# dsau-interfaces.net
KiCad netlist of a schematic drawn in Altium Designer
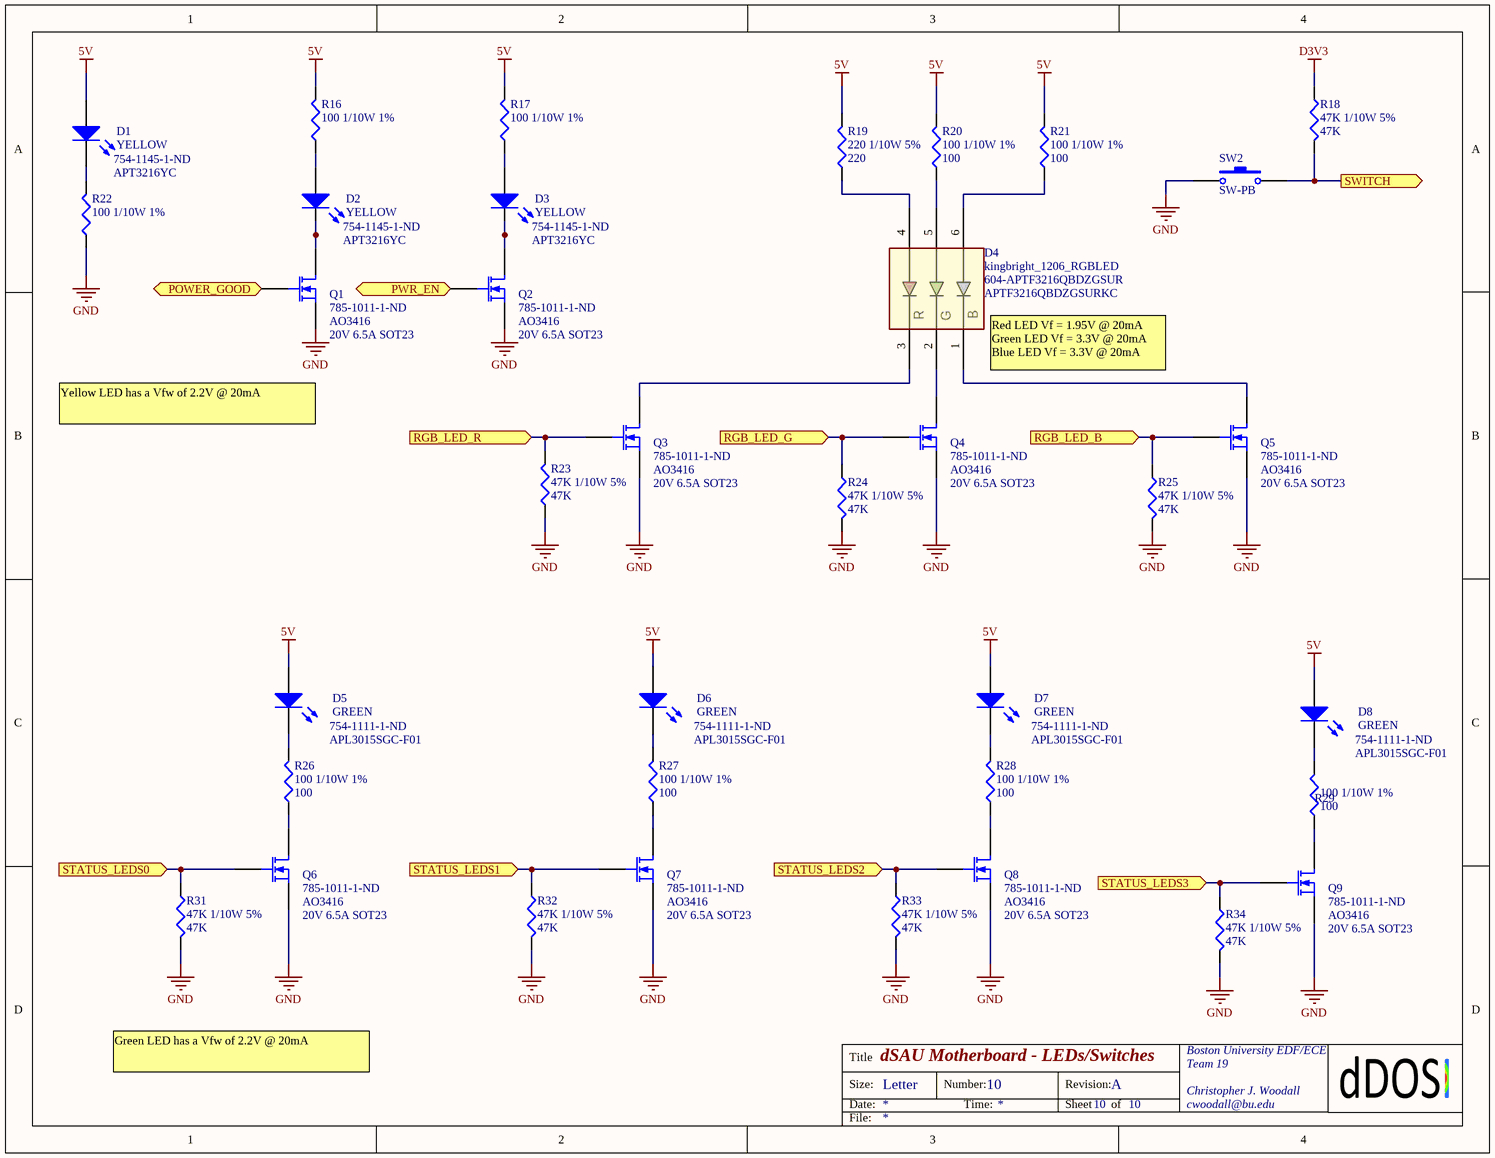
[diagram p0: dsau-interfaces.SchDoc]

(export (version "E")
  (design (tool "Eeschema 10.0.6"))
  (components
    (comp (ref "D1")
      (value "YELLOW")
      (footprint "LED3216X08M")
      (description "Typical INFRARED GaAs LED")
      (fields
        (field (name "MANUFACTURER") "Kingbright Company LLC")
        (field (name "MANUFACTURER PART NUMBER") "APT3216YC")
        (field (name "SUPPLIER PART NUMBER 1") "754-1145-1-ND")
        (field (name "PUBLISHER") "Altium Limited")
      )
      (libsource (lib "Miscellaneous Devices") (part "LED0"))
    )
    (comp (ref "D2")
      (value "YELLOW")
      (footprint "LED3216X08M")
      (description "Typical INFRARED GaAs LED")
      (fields
        (field (name "MANUFACTURER") "Kingbright Company LLC")
        (field (name "MANUFACTURER PART NUMBER") "APT3216YC")
        (field (name "SUPPLIER PART NUMBER 1") "754-1145-1-ND")
        (field (name "PUBLISHER") "Altium Limited")
      )
      (libsource (lib "Miscellaneous Devices") (part "LED0"))
    )
    (comp (ref "D3")
      (value "YELLOW")
      (footprint "LED3216X08M")
      (description "Typical INFRARED GaAs LED")
      (fields
        (field (name "MANUFACTURER") "Kingbright Company LLC")
        (field (name "MANUFACTURER PART NUMBER") "APT3216YC")
        (field (name "SUPPLIER PART NUMBER 1") "754-1145-1-ND")
        (field (name "PUBLISHER") "Altium Limited")
      )
      (libsource (lib "Miscellaneous Devices") (part "LED0"))
    )
    (comp (ref "D4")
      (value "kingbright_1206_RGBLED")
      (footprint "RGBLED_1206_KINGSBRIGHT")
      (fields
        (field (name "SUPPLIER PART NUMBER 1") "604-APTF3216QBDZGSUR")
        (field (name "MANUFACTURER") "Kingbright")
        (field (name "MANUFACTURER PART NUMBER") "APTF3216QBDZGSURKC")
      )
      (libsource (lib "dsau-motherboard") (part "kingbright_1206_RGBLED"))
    )
    (comp (ref "D5")
      (value "GREEN")
      (footprint "LED3216X08M")
      (description "Typical INFRARED GaAs LED")
      (fields
        (field (name "MANUFACTURER") "Kingbright Company LLC")
        (field (name "MANUFACTURER PART NUMBER") "APL3015SGC-F01")
        (field (name "SUPPLIER PART NUMBER 1") "754-1111-1-ND")
        (field (name "PUBLISHER") "Altium Limited")
      )
      (libsource (lib "Miscellaneous Devices") (part "LED0"))
    )
    (comp (ref "D6")
      (value "GREEN")
      (footprint "LED3216X08M")
      (description "Typical INFRARED GaAs LED")
      (fields
        (field (name "MANUFACTURER") "Kingbright Company LLC")
        (field (name "MANUFACTURER PART NUMBER") "APL3015SGC-F01")
        (field (name "SUPPLIER PART NUMBER 1") "754-1111-1-ND")
        (field (name "PUBLISHER") "Altium Limited")
      )
      (libsource (lib "Miscellaneous Devices") (part "LED0"))
    )
    (comp (ref "D7")
      (value "GREEN")
      (footprint "LED3216X08M")
      (description "Typical INFRARED GaAs LED")
      (fields
        (field (name "MANUFACTURER") "Kingbright Company LLC")
        (field (name "MANUFACTURER PART NUMBER") "APL3015SGC-F01")
        (field (name "SUPPLIER PART NUMBER 1") "754-1111-1-ND")
        (field (name "PUBLISHER") "Altium Limited")
      )
      (libsource (lib "Miscellaneous Devices") (part "LED0"))
    )
    (comp (ref "D8")
      (value "GREEN")
      (footprint "LED3216X08M")
      (description "Typical INFRARED GaAs LED")
      (fields
        (field (name "MANUFACTURER") "Kingbright Company LLC")
        (field (name "MANUFACTURER PART NUMBER") "APL3015SGC-F01")
        (field (name "SUPPLIER PART NUMBER 1") "754-1111-1-ND")
        (field (name "PUBLISHER") "Altium Limited")
      )
      (libsource (lib "Miscellaneous Devices") (part "LED0"))
    )
    (comp (ref "Q1")
      (value "20V 6.5A SOT23")
      (footprint "SOT95P305X200-3M")
      (description "N-Channel MOSFET 1.8V Logic Level")
      (fields
        (field (name "MANUFACTURER") "Alpha & Omega Semiconductor Inc")
        (field (name "MANUFACTURER PART NUMBER") "AO3416")
        (field (name "SUPPLIER PART NUMBER 1") "785-1011-1-ND")
        (field (name "PUBLISHER") "Altium Limited")
      )
      (libsource (lib "Miscellaneous Devices") (part "MOSFET-N"))
    )
    (comp (ref "Q2")
      (value "20V 6.5A SOT23")
      (footprint "SOT95P305X200-3M")
      (description "N-Channel MOSFET 1.8V Logic Level")
      (fields
        (field (name "MANUFACTURER") "Alpha & Omega Semiconductor Inc")
        (field (name "MANUFACTURER PART NUMBER") "AO3416")
        (field (name "SUPPLIER PART NUMBER 1") "785-1011-1-ND")
        (field (name "PUBLISHER") "Altium Limited")
      )
      (libsource (lib "Miscellaneous Devices") (part "MOSFET-N"))
    )
    (comp (ref "Q3")
      (value "20V 6.5A SOT23")
      (footprint "SOT95P305X200-3M")
      (description "N-Channel MOSFET 1.8V Logic Level")
      (fields
        (field (name "MANUFACTURER") "Alpha & Omega Semiconductor Inc")
        (field (name "MANUFACTURER PART NUMBER") "AO3416")
        (field (name "SUPPLIER PART NUMBER 1") "785-1011-1-ND")
        (field (name "PUBLISHER") "Altium Limited")
      )
      (libsource (lib "Miscellaneous Devices") (part "MOSFET-N"))
    )
    (comp (ref "Q4")
      (value "20V 6.5A SOT23")
      (footprint "SOT95P305X200-3M")
      (description "N-Channel MOSFET 1.8V Logic Level")
      (fields
        (field (name "MANUFACTURER") "Alpha & Omega Semiconductor Inc")
        (field (name "MANUFACTURER PART NUMBER") "AO3416")
        (field (name "SUPPLIER PART NUMBER 1") "785-1011-1-ND")
        (field (name "PUBLISHER") "Altium Limited")
      )
      (libsource (lib "Miscellaneous Devices") (part "MOSFET-N"))
    )
    (comp (ref "Q5")
      (value "20V 6.5A SOT23")
      (footprint "SOT95P305X200-3M")
      (description "N-Channel MOSFET 1.8V Logic Level")
      (fields
        (field (name "MANUFACTURER") "Alpha & Omega Semiconductor Inc")
        (field (name "MANUFACTURER PART NUMBER") "AO3416")
        (field (name "SUPPLIER PART NUMBER 1") "785-1011-1-ND")
        (field (name "PUBLISHER") "Altium Limited")
      )
      (libsource (lib "Miscellaneous Devices") (part "MOSFET-N"))
    )
    (comp (ref "Q6")
      (value "20V 6.5A SOT23")
      (footprint "SOT95P305X200-3M")
      (description "N-Channel MOSFET 1.8V Logic Level")
      (fields
        (field (name "MANUFACTURER") "Alpha & Omega Semiconductor Inc")
        (field (name "MANUFACTURER PART NUMBER") "AO3416")
        (field (name "SUPPLIER PART NUMBER 1") "785-1011-1-ND")
        (field (name "PUBLISHER") "Altium Limited")
      )
      (libsource (lib "Miscellaneous Devices") (part "MOSFET-N"))
    )
    (comp (ref "Q7")
      (value "20V 6.5A SOT23")
      (footprint "SOT95P305X200-3M")
      (description "N-Channel MOSFET 1.8V Logic Level")
      (fields
        (field (name "MANUFACTURER") "Alpha & Omega Semiconductor Inc")
        (field (name "MANUFACTURER PART NUMBER") "AO3416")
        (field (name "SUPPLIER PART NUMBER 1") "785-1011-1-ND")
        (field (name "PUBLISHER") "Altium Limited")
      )
      (libsource (lib "Miscellaneous Devices") (part "MOSFET-N"))
    )
    (comp (ref "Q8")
      (value "20V 6.5A SOT23")
      (footprint "SOT95P305X200-3M")
      (description "N-Channel MOSFET 1.8V Logic Level")
      (fields
        (field (name "MANUFACTURER") "Alpha & Omega Semiconductor Inc")
        (field (name "MANUFACTURER PART NUMBER") "AO3416")
        (field (name "SUPPLIER PART NUMBER 1") "785-1011-1-ND")
        (field (name "PUBLISHER") "Altium Limited")
      )
      (libsource (lib "Miscellaneous Devices") (part "MOSFET-N"))
    )
    (comp (ref "Q9")
      (value "20V 6.5A SOT23")
      (footprint "SOT95P305X200-3M")
      (description "N-Channel MOSFET 1.8V Logic Level")
      (fields
        (field (name "MANUFACTURER") "Alpha & Omega Semiconductor Inc")
        (field (name "MANUFACTURER PART NUMBER") "AO3416")
        (field (name "SUPPLIER PART NUMBER 1") "785-1011-1-ND")
        (field (name "PUBLISHER") "Altium Limited")
      )
      (libsource (lib "Miscellaneous Devices") (part "MOSFET-N"))
    )
    (comp (ref "R16")
      (value "100 1/10W 1%")
      (footprint "RESC1608L")
      (description "Resistor")
      (fields
        (field (name "MANUFACTURER") "Yageo")
        (field (name "MANUFACTURER PART NUMBER") "RC0603FR-07100RL")
        (field (name "PUBLISHER") "Altium Limited")
      )
      (libsource (lib "Miscellaneous Devices") (part "Res3"))
    )
    (comp (ref "R17")
      (value "100 1/10W 1%")
      (footprint "RESC1608L")
      (description "Resistor")
      (fields
        (field (name "MANUFACTURER") "Yageo")
        (field (name "MANUFACTURER PART NUMBER") "RC0603FR-07100RL")
        (field (name "PUBLISHER") "Altium Limited")
      )
      (libsource (lib "Miscellaneous Devices") (part "Res3"))
    )
    (comp (ref "R18")
      (value "47K 1/10W 5%")
      (footprint "RESC1608L")
      (description "Resistor")
      (fields
        (field (name "ALTIUM_VALUE") "47K")
        (field (name "MANUFACTURER") "Yageo")
        (field (name "MANUFACTURER PART NUMBER") "311-47kGRCT-ND")
        (field (name "PUBLISHER") "Altium Limited")
      )
      (libsource (lib "Miscellaneous Devices") (part "Res3"))
    )
    (comp (ref "R19")
      (value "220 1/10W 5%")
      (footprint "RESC1608L")
      (description "Resistor")
      (fields
        (field (name "ALTIUM_VALUE") "220")
        (field (name "MANUFACTURER") "Yageo")
        (field (name "MANUFACTURER PART NUMBER") "RC0603FR-07220RL")
        (field (name "PUBLISHER") "Altium Limited")
      )
      (libsource (lib "Miscellaneous Devices") (part "Res3"))
    )
    (comp (ref "R20")
      (value "100 1/10W 1%")
      (footprint "RESC1608L")
      (description "Resistor")
      (fields
        (field (name "ALTIUM_VALUE") "100")
        (field (name "MANUFACTURER") "Yageo")
        (field (name "MANUFACTURER PART NUMBER") "RC0603FR-07100RL")
        (field (name "PUBLISHER") "Altium Limited")
      )
      (libsource (lib "Miscellaneous Devices") (part "Res3"))
    )
    (comp (ref "R21")
      (value "100 1/10W 1%")
      (footprint "RESC1608L")
      (description "Resistor")
      (fields
        (field (name "ALTIUM_VALUE") "100")
        (field (name "MANUFACTURER") "Yageo")
        (field (name "MANUFACTURER PART NUMBER") "RC0603FR-07100RL")
        (field (name "PUBLISHER") "Altium Limited")
      )
      (libsource (lib "Miscellaneous Devices") (part "Res3"))
    )
    (comp (ref "R22")
      (value "100 1/10W 1%")
      (footprint "RESC1608L")
      (description "Resistor")
      (fields
        (field (name "MANUFACTURER") "Yageo")
        (field (name "MANUFACTURER PART NUMBER") "RC0603FR-07100RL")
        (field (name "PUBLISHER") "Altium Limited")
      )
      (libsource (lib "Miscellaneous Devices") (part "Res3"))
    )
    (comp (ref "R23")
      (value "47K 1/10W 5%")
      (footprint "RESC1608L")
      (description "Resistor")
      (fields
        (field (name "ALTIUM_VALUE") "47K")
        (field (name "MANUFACTURER") "Yageo")
        (field (name "MANUFACTURER PART NUMBER") "311-47kGRCT-ND")
        (field (name "PUBLISHER") "Altium Limited")
      )
      (libsource (lib "Miscellaneous Devices") (part "Res3"))
    )
    (comp (ref "R24")
      (value "47K 1/10W 5%")
      (footprint "RESC1608L")
      (description "Resistor")
      (fields
        (field (name "ALTIUM_VALUE") "47K")
        (field (name "MANUFACTURER") "Yageo")
        (field (name "MANUFACTURER PART NUMBER") "311-47kGRCT-ND")
        (field (name "PUBLISHER") "Altium Limited")
      )
      (libsource (lib "Miscellaneous Devices") (part "Res3"))
    )
    (comp (ref "R25")
      (value "47K 1/10W 5%")
      (footprint "RESC1608L")
      (description "Resistor")
      (fields
        (field (name "ALTIUM_VALUE") "47K")
        (field (name "MANUFACTURER") "Yageo")
        (field (name "MANUFACTURER PART NUMBER") "311-47kGRCT-ND")
        (field (name "PUBLISHER") "Altium Limited")
      )
      (libsource (lib "Miscellaneous Devices") (part "Res3"))
    )
    (comp (ref "R26")
      (value "100 1/10W 1%")
      (footprint "RESC1608L")
      (description "Resistor")
      (fields
        (field (name "ALTIUM_VALUE") "100")
        (field (name "MANUFACTURER") "Yageo")
        (field (name "MANUFACTURER PART NUMBER") "RC0603FR-07100RL")
        (field (name "PUBLISHER") "Altium Limited")
      )
      (libsource (lib "Miscellaneous Devices") (part "Res3"))
    )
    (comp (ref "R27")
      (value "100 1/10W 1%")
      (footprint "RESC1608L")
      (description "Resistor")
      (fields
        (field (name "ALTIUM_VALUE") "100")
        (field (name "MANUFACTURER") "Yageo")
        (field (name "MANUFACTURER PART NUMBER") "RC0603FR-07100RL")
        (field (name "PUBLISHER") "Altium Limited")
      )
      (libsource (lib "Miscellaneous Devices") (part "Res3"))
    )
    (comp (ref "R28")
      (value "100 1/10W 1%")
      (footprint "RESC1608L")
      (description "Resistor")
      (fields
        (field (name "ALTIUM_VALUE") "100")
        (field (name "MANUFACTURER") "Yageo")
        (field (name "MANUFACTURER PART NUMBER") "RC0603FR-07100RL")
        (field (name "PUBLISHER") "Altium Limited")
      )
      (libsource (lib "Miscellaneous Devices") (part "Res3"))
    )
    (comp (ref "R29")
      (value "100 1/10W 1%")
      (footprint "RESC1608L")
      (description "Resistor")
      (fields
        (field (name "ALTIUM_VALUE") "100")
        (field (name "MANUFACTURER") "Yageo")
        (field (name "MANUFACTURER PART NUMBER") "RC0603FR-07100RL")
        (field (name "PUBLISHER") "Altium Limited")
      )
      (libsource (lib "Miscellaneous Devices") (part "Res3"))
    )
    (comp (ref "R31")
      (value "47K 1/10W 5%")
      (footprint "RESC1608L")
      (description "Resistor")
      (fields
        (field (name "ALTIUM_VALUE") "47K")
        (field (name "MANUFACTURER") "Yageo")
        (field (name "MANUFACTURER PART NUMBER") "311-47kGRCT-ND")
        (field (name "PUBLISHER") "Altium Limited")
      )
      (libsource (lib "Miscellaneous Devices") (part "Res3"))
    )
    (comp (ref "R32")
      (value "47K 1/10W 5%")
      (footprint "RESC1608L")
      (description "Resistor")
      (fields
        (field (name "ALTIUM_VALUE") "47K")
        (field (name "MANUFACTURER") "Yageo")
        (field (name "MANUFACTURER PART NUMBER") "311-47kGRCT-ND")
        (field (name "PUBLISHER") "Altium Limited")
      )
      (libsource (lib "Miscellaneous Devices") (part "Res3"))
    )
    (comp (ref "R33")
      (value "47K 1/10W 5%")
      (footprint "RESC1608L")
      (description "Resistor")
      (fields
        (field (name "ALTIUM_VALUE") "47K")
        (field (name "MANUFACTURER") "Yageo")
        (field (name "MANUFACTURER PART NUMBER") "311-47kGRCT-ND")
        (field (name "PUBLISHER") "Altium Limited")
      )
      (libsource (lib "Miscellaneous Devices") (part "Res3"))
    )
    (comp (ref "R34")
      (value "47K 1/10W 5%")
      (footprint "RESC1608L")
      (description "Resistor")
      (fields
        (field (name "ALTIUM_VALUE") "47K")
        (field (name "MANUFACTURER") "Yageo")
        (field (name "MANUFACTURER PART NUMBER") "311-47kGRCT-ND")
        (field (name "PUBLISHER") "Altium Limited")
      )
      (libsource (lib "Miscellaneous Devices") (part "Res3"))
    )
    (comp (ref "SW2")
      (value "SW-PB")
      (footprint "SPST_SW_FSM4JH")
      (description "Switch")
      (fields
        (field (name "MANUFACTURER") "TE Connectivity")
        (field (name "MANUFACTURER PART NUMBER") "FSM4JH")
        (field (name "PUBLISHER") "Altium Limited")
      )
      (libsource (lib "Miscellaneous Devices") (part "SW-PB"))
    )
  )
  (nets
    (net (code "1") (name "/POWER_GOOD") (class "Default")
      (node (ref "Q1") (pin "1") (pinfunction "G_1") (pintype "passive"))
    )
    (net (code "2") (name "/PWR_EN") (class "Default")
      (node (ref "Q2") (pin "1") (pinfunction "G_1") (pintype "passive"))
    )
    (net (code "3") (name "/RGB_LED_B") (class "Default")
      (node (ref "Q5") (pin "1") (pinfunction "G_1") (pintype "passive"))
      (node (ref "R25") (pin "1") (pinfunction "1_1") (pintype "passive"))
    )
    (net (code "4") (name "/RGB_LED_G") (class "Default")
      (node (ref "Q4") (pin "1") (pinfunction "G_1") (pintype "passive"))
      (node (ref "R24") (pin "1") (pinfunction "1_1") (pintype "passive"))
    )
    (net (code "5") (name "/RGB_LED_R") (class "Default")
      (node (ref "Q3") (pin "1") (pinfunction "G_1") (pintype "passive"))
      (node (ref "R23") (pin "2") (pinfunction "2_2") (pintype "passive"))
    )
    (net (code "6") (name "/STATUS_LEDS0") (class "Default")
      (node (ref "Q6") (pin "1") (pinfunction "G_1") (pintype "passive"))
      (node (ref "R31") (pin "1") (pinfunction "1_1") (pintype "passive"))
    )
    (net (code "7") (name "/STATUS_LEDS1") (class "Default")
      (node (ref "Q7") (pin "1") (pinfunction "G_1") (pintype "passive"))
      (node (ref "R32") (pin "1") (pinfunction "1_1") (pintype "passive"))
    )
    (net (code "8") (name "/STATUS_LEDS2") (class "Default")
      (node (ref "Q8") (pin "1") (pinfunction "G_1") (pintype "passive"))
      (node (ref "R33") (pin "1") (pinfunction "1_1") (pintype "passive"))
    )
    (net (code "9") (name "/STATUS_LEDS3") (class "Default")
      (node (ref "Q9") (pin "1") (pinfunction "G_1") (pintype "passive"))
      (node (ref "R34") (pin "1") (pinfunction "1_1") (pintype "passive"))
    )
    (net (code "10") (name "/SWITCH") (class "Default")
      (node (ref "R18") (pin "2") (pinfunction "2_2") (pintype "passive"))
      (node (ref "SW2") (pin "1") (pinfunction "1_1") (pintype "passive"))
    )
    (net (code "11") (name "5V") (class "Default")
      (node (ref "D1") (pin "1") (pinfunction "A_1") (pintype "passive"))
      (node (ref "D5") (pin "1") (pinfunction "A_1") (pintype "passive"))
      (node (ref "D6") (pin "1") (pinfunction "A_1") (pintype "passive"))
      (node (ref "D7") (pin "1") (pinfunction "A_1") (pintype "passive"))
      (node (ref "D8") (pin "1") (pinfunction "A_1") (pintype "passive"))
      (node (ref "R16") (pin "2") (pinfunction "2_2") (pintype "passive"))
      (node (ref "R17") (pin "2") (pinfunction "2_2") (pintype "passive"))
      (node (ref "R19") (pin "2") (pinfunction "2_2") (pintype "passive"))
      (node (ref "R20") (pin "2") (pinfunction "2_2") (pintype "passive"))
      (node (ref "R21") (pin "2") (pinfunction "2_2") (pintype "passive"))
    )
    (net (code "12") (name "D3V3") (class "Default")
      (node (ref "R18") (pin "1") (pinfunction "1_1") (pintype "passive"))
    )
    (net (code "13") (name "GND") (class "Default")
      (node (ref "Q1") (pin "2") (pinfunction "S_2") (pintype "passive"))
      (node (ref "Q2") (pin "2") (pinfunction "S_2") (pintype "passive"))
      (node (ref "Q3") (pin "2") (pinfunction "S_2") (pintype "passive"))
      (node (ref "Q4") (pin "2") (pinfunction "S_2") (pintype "passive"))
      (node (ref "Q5") (pin "2") (pinfunction "S_2") (pintype "passive"))
      (node (ref "Q6") (pin "2") (pinfunction "S_2") (pintype "passive"))
      (node (ref "Q7") (pin "2") (pinfunction "S_2") (pintype "passive"))
      (node (ref "Q8") (pin "2") (pinfunction "S_2") (pintype "passive"))
      (node (ref "Q9") (pin "2") (pinfunction "S_2") (pintype "passive"))
      (node (ref "R22") (pin "1") (pinfunction "1_1") (pintype "passive"))
      (node (ref "R23") (pin "1") (pinfunction "1_1") (pintype "passive"))
      (node (ref "R24") (pin "2") (pinfunction "2_2") (pintype "passive"))
      (node (ref "R25") (pin "2") (pinfunction "2_2") (pintype "passive"))
      (node (ref "R31") (pin "2") (pinfunction "2_2") (pintype "passive"))
      (node (ref "R32") (pin "2") (pinfunction "2_2") (pintype "passive"))
      (node (ref "R33") (pin "2") (pinfunction "2_2") (pintype "passive"))
      (node (ref "R34") (pin "2") (pinfunction "2_2") (pintype "passive"))
      (node (ref "SW2") (pin "2") (pinfunction "2_2") (pintype "passive"))
    )
    (net (code "14") (name "Net-(D1-K)") (class "Default")
      (node (ref "D1") (pin "2") (pinfunction "K_2") (pintype "passive"))
      (node (ref "R22") (pin "2") (pinfunction "2_2") (pintype "passive"))
    )
    (net (code "15") (name "Net-(D2-A)") (class "Default")
      (node (ref "D2") (pin "1") (pinfunction "A_1") (pintype "passive"))
      (node (ref "R16") (pin "1") (pinfunction "1_1") (pintype "passive"))
    )
    (net (code "16") (name "Net-(D2-K)") (class "Default")
      (node (ref "D2") (pin "2") (pinfunction "K_2") (pintype "passive"))
      (node (ref "Q1") (pin "3") (pinfunction "D_3") (pintype "passive"))
    )
    (net (code "17") (name "Net-(D3-A)") (class "Default")
      (node (ref "D3") (pin "1") (pinfunction "A_1") (pintype "passive"))
      (node (ref "R17") (pin "1") (pinfunction "1_1") (pintype "passive"))
    )
    (net (code "18") (name "Net-(D3-K)") (class "Default")
      (node (ref "D3") (pin "2") (pinfunction "K_2") (pintype "passive"))
      (node (ref "Q2") (pin "3") (pinfunction "D_3") (pintype "passive"))
    )
    (net (code "19") (name "Net-(D4-B_N)") (class "Default")
      (node (ref "D4") (pin "1") (pinfunction "B_N_1") (pintype "passive"))
      (node (ref "Q5") (pin "3") (pinfunction "D_3") (pintype "passive"))
    )
    (net (code "20") (name "Net-(D4-B_P)") (class "Default")
      (node (ref "D4") (pin "6") (pinfunction "B_P_6") (pintype "passive"))
      (node (ref "R21") (pin "1") (pinfunction "1_1") (pintype "passive"))
    )
    (net (code "21") (name "Net-(D4-G_N)") (class "Default")
      (node (ref "D4") (pin "2") (pinfunction "G_N_2") (pintype "passive"))
      (node (ref "Q4") (pin "3") (pinfunction "D_3") (pintype "passive"))
    )
    (net (code "22") (name "Net-(D4-G_P)") (class "Default")
      (node (ref "D4") (pin "5") (pinfunction "G_P_5") (pintype "passive"))
      (node (ref "R20") (pin "1") (pinfunction "1_1") (pintype "passive"))
    )
    (net (code "23") (name "Net-(D4-R_N)") (class "Default")
      (node (ref "D4") (pin "3") (pinfunction "R_N_3") (pintype "passive"))
      (node (ref "Q3") (pin "3") (pinfunction "D_3") (pintype "passive"))
    )
    (net (code "24") (name "Net-(D4-R_P)") (class "Default")
      (node (ref "D4") (pin "4") (pinfunction "R_P_4") (pintype "passive"))
      (node (ref "R19") (pin "1") (pinfunction "1_1") (pintype "passive"))
    )
    (net (code "25") (name "Net-(D5-K)") (class "Default")
      (node (ref "D5") (pin "2") (pinfunction "K_2") (pintype "passive"))
      (node (ref "R26") (pin "2") (pinfunction "2_2") (pintype "passive"))
    )
    (net (code "26") (name "Net-(D6-K)") (class "Default")
      (node (ref "D6") (pin "2") (pinfunction "K_2") (pintype "passive"))
      (node (ref "R27") (pin "2") (pinfunction "2_2") (pintype "passive"))
    )
    (net (code "27") (name "Net-(D7-K)") (class "Default")
      (node (ref "D7") (pin "2") (pinfunction "K_2") (pintype "passive"))
      (node (ref "R28") (pin "2") (pinfunction "2_2") (pintype "passive"))
    )
    (net (code "28") (name "Net-(D8-K)") (class "Default")
      (node (ref "D8") (pin "2") (pinfunction "K_2") (pintype "passive"))
      (node (ref "R29") (pin "2") (pinfunction "2_2") (pintype "passive"))
    )
    (net (code "29") (name "Net-(Q6-D)") (class "Default")
      (node (ref "Q6") (pin "3") (pinfunction "D_3") (pintype "passive"))
      (node (ref "R26") (pin "1") (pinfunction "1_1") (pintype "passive"))
    )
    (net (code "30") (name "Net-(Q7-D)") (class "Default")
      (node (ref "Q7") (pin "3") (pinfunction "D_3") (pintype "passive"))
      (node (ref "R27") (pin "1") (pinfunction "1_1") (pintype "passive"))
    )
    (net (code "31") (name "Net-(Q8-D)") (class "Default")
      (node (ref "Q8") (pin "3") (pinfunction "D_3") (pintype "passive"))
      (node (ref "R28") (pin "1") (pinfunction "1_1") (pintype "passive"))
    )
    (net (code "32") (name "Net-(Q9-D)") (class "Default")
      (node (ref "Q9") (pin "3") (pinfunction "D_3") (pintype "passive"))
      (node (ref "R29") (pin "1") (pinfunction "1_1") (pintype "passive"))
    )
  )
)
